# Beacon.net
KiCad netlist of a schematic drawn in EAGLE
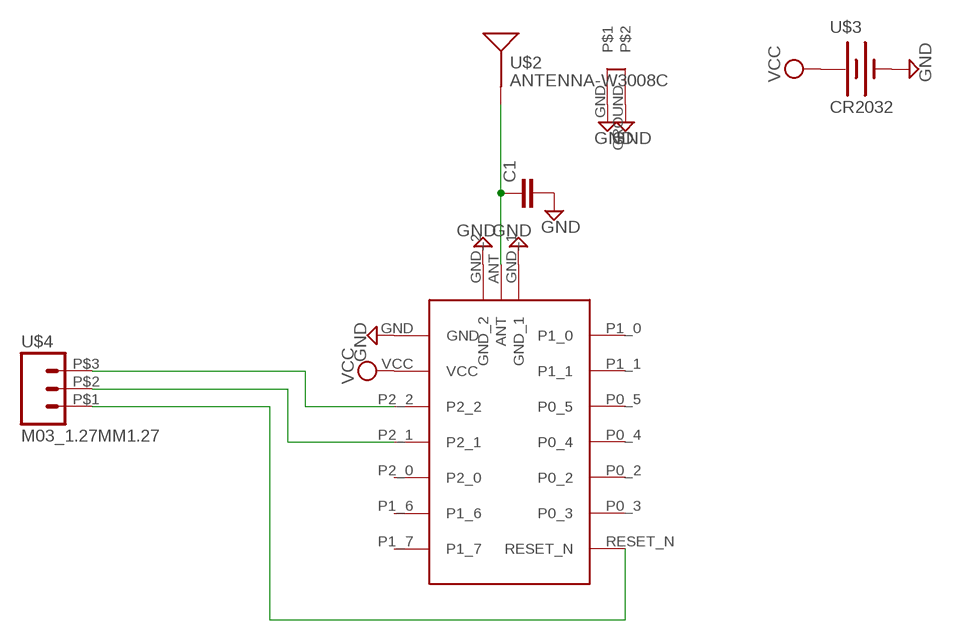
[diagram p0: schematic, sheet 1]

(export (version "E")
  (design (tool "Eeschema 10.0.6"))
  (components
    (comp (ref "C1")
      (value "CAP0402-CAP")
      (footprint "eagle-import:0402-CAP")
      (libsource (lib "eagle-import") (part "CAP0402-CAP"))
    )
    (comp (ref "U$1")
      (value "BLE4")
      (footprint "eagle-import:BLE4")
      (libsource (lib "eagle-import") (part "BLE4"))
    )
    (comp (ref "U$2")
      (value "ANTENNA-W3008C")
      (footprint "eagle-import:ANTENNA-W3008C")
      (libsource (lib "eagle-import") (part "ANTENNA-W3008C"))
    )
    (comp (ref "U$3")
      (value "CR2032")
      (footprint "eagle-import:BATTCON_2032")
      (libsource (lib "eagle-import") (part "CR2032"))
    )
    (comp (ref "U$4")
      (value "M03_1.27MM1.27")
      (footprint "eagle-import:1X3_1.27MM")
      (libsource (lib "eagle-import") (part "M03_1.27MM1.27"))
    )
  )
  (nets
    (net (code "1") (name "GND") (class "Default")
      (node (ref "C1") (pin "2") (pinfunction "2_2") (pintype "passive"))
      (node (ref "U$1") (pin "GND") (pinfunction "GND_GND") (pintype "bidirectional"))
      (node (ref "U$1") (pin "GND_1") (pinfunction "GND_1_GND_1") (pintype "bidirectional"))
      (node (ref "U$1") (pin "GND_2") (pinfunction "GND_2_GND_2") (pintype "bidirectional"))
      (node (ref "U$2") (pin "GND") (pinfunction "P$1_GND") (pintype "bidirectional"))
      (node (ref "U$2") (pin "GROUND") (pinfunction "P$2_GROUND") (pintype "bidirectional"))
      (node (ref "U$3") (pin "PWR@2") (pinfunction "-_PWR@2") (pintype "power_in"))
    )
    (net (code "2") (name "Net-(U$2-SIGNAL)") (class "Default")
      (node (ref "C1") (pin "1") (pinfunction "1_1") (pintype "passive"))
      (node (ref "U$1") (pin "ANT") (pinfunction "ANT_ANT") (pintype "bidirectional"))
      (node (ref "U$2") (pin "FEED") (pinfunction "SIGNAL_FEED") (pintype "bidirectional"))
    )
    (net (code "3") (name "Net-(U$4-1)") (class "Default")
      (node (ref "U$1") (pin "RESET_N") (pinfunction "RESET_N_RESET_N") (pintype "bidirectional"))
      (node (ref "U$4") (pin "P$1") (pinfunction "1_P$1") (pintype "passive"))
    )
    (net (code "4") (name "Net-(U$4-2)") (class "Default")
      (node (ref "U$1") (pin "P2_1") (pinfunction "P2_1_P2_1") (pintype "bidirectional"))
      (node (ref "U$4") (pin "P$2") (pinfunction "2_P$2") (pintype "passive"))
    )
    (net (code "5") (name "Net-(U$4-3)") (class "Default")
      (node (ref "U$1") (pin "P2_2") (pinfunction "P2_2_P2_2") (pintype "bidirectional"))
      (node (ref "U$4") (pin "P$3") (pinfunction "3_P$3") (pintype "passive"))
    )
    (net (code "6") (name "VCC") (class "Default")
      (node (ref "U$1") (pin "VCC") (pinfunction "VCC_VCC") (pintype "bidirectional"))
      (node (ref "U$3") (pin "PWR@1") (pinfunction "+_PWR@1") (pintype "power_in"))
    )
    (net (code "7") (name "unconnected-(U$1-PadP0_2)") (class "Default")
      (node (ref "U$1") (pin "P0_2") (pinfunction "P0_2_P0_2") (pintype "bidirectional"))
    )
    (net (code "8") (name "unconnected-(U$1-PadP0_3)") (class "Default")
      (node (ref "U$1") (pin "P0_3") (pinfunction "P0_3_P0_3") (pintype "bidirectional"))
    )
    (net (code "9") (name "unconnected-(U$1-PadP0_4)") (class "Default")
      (node (ref "U$1") (pin "P0_4") (pinfunction "P0_4_P0_4") (pintype "bidirectional"))
    )
    (net (code "10") (name "unconnected-(U$1-PadP0_5)") (class "Default")
      (node (ref "U$1") (pin "P0_5") (pinfunction "P0_5_P0_5") (pintype "bidirectional"))
    )
    (net (code "11") (name "unconnected-(U$1-PadP1_0)") (class "Default")
      (node (ref "U$1") (pin "P1_0") (pinfunction "P1_0_P1_0") (pintype "bidirectional"))
    )
    (net (code "12") (name "unconnected-(U$1-PadP1_1)") (class "Default")
      (node (ref "U$1") (pin "P1_1") (pinfunction "P1_1_P1_1") (pintype "bidirectional"))
    )
    (net (code "13") (name "unconnected-(U$1-PadP1_6)") (class "Default")
      (node (ref "U$1") (pin "P1_6") (pinfunction "P1_6_P1_6") (pintype "bidirectional"))
    )
    (net (code "14") (name "unconnected-(U$1-PadP1_7)") (class "Default")
      (node (ref "U$1") (pin "P1_7") (pinfunction "P1_7_P1_7") (pintype "bidirectional"))
    )
    (net (code "15") (name "unconnected-(U$1-PadP2_0)") (class "Default")
      (node (ref "U$1") (pin "P2_0") (pinfunction "P2_0_P2_0") (pintype "bidirectional"))
    )
  )
)
